# CircuitSupply_v1_0_3.net
KiCad netlist of a schematic drawn in EasyEDA Pro
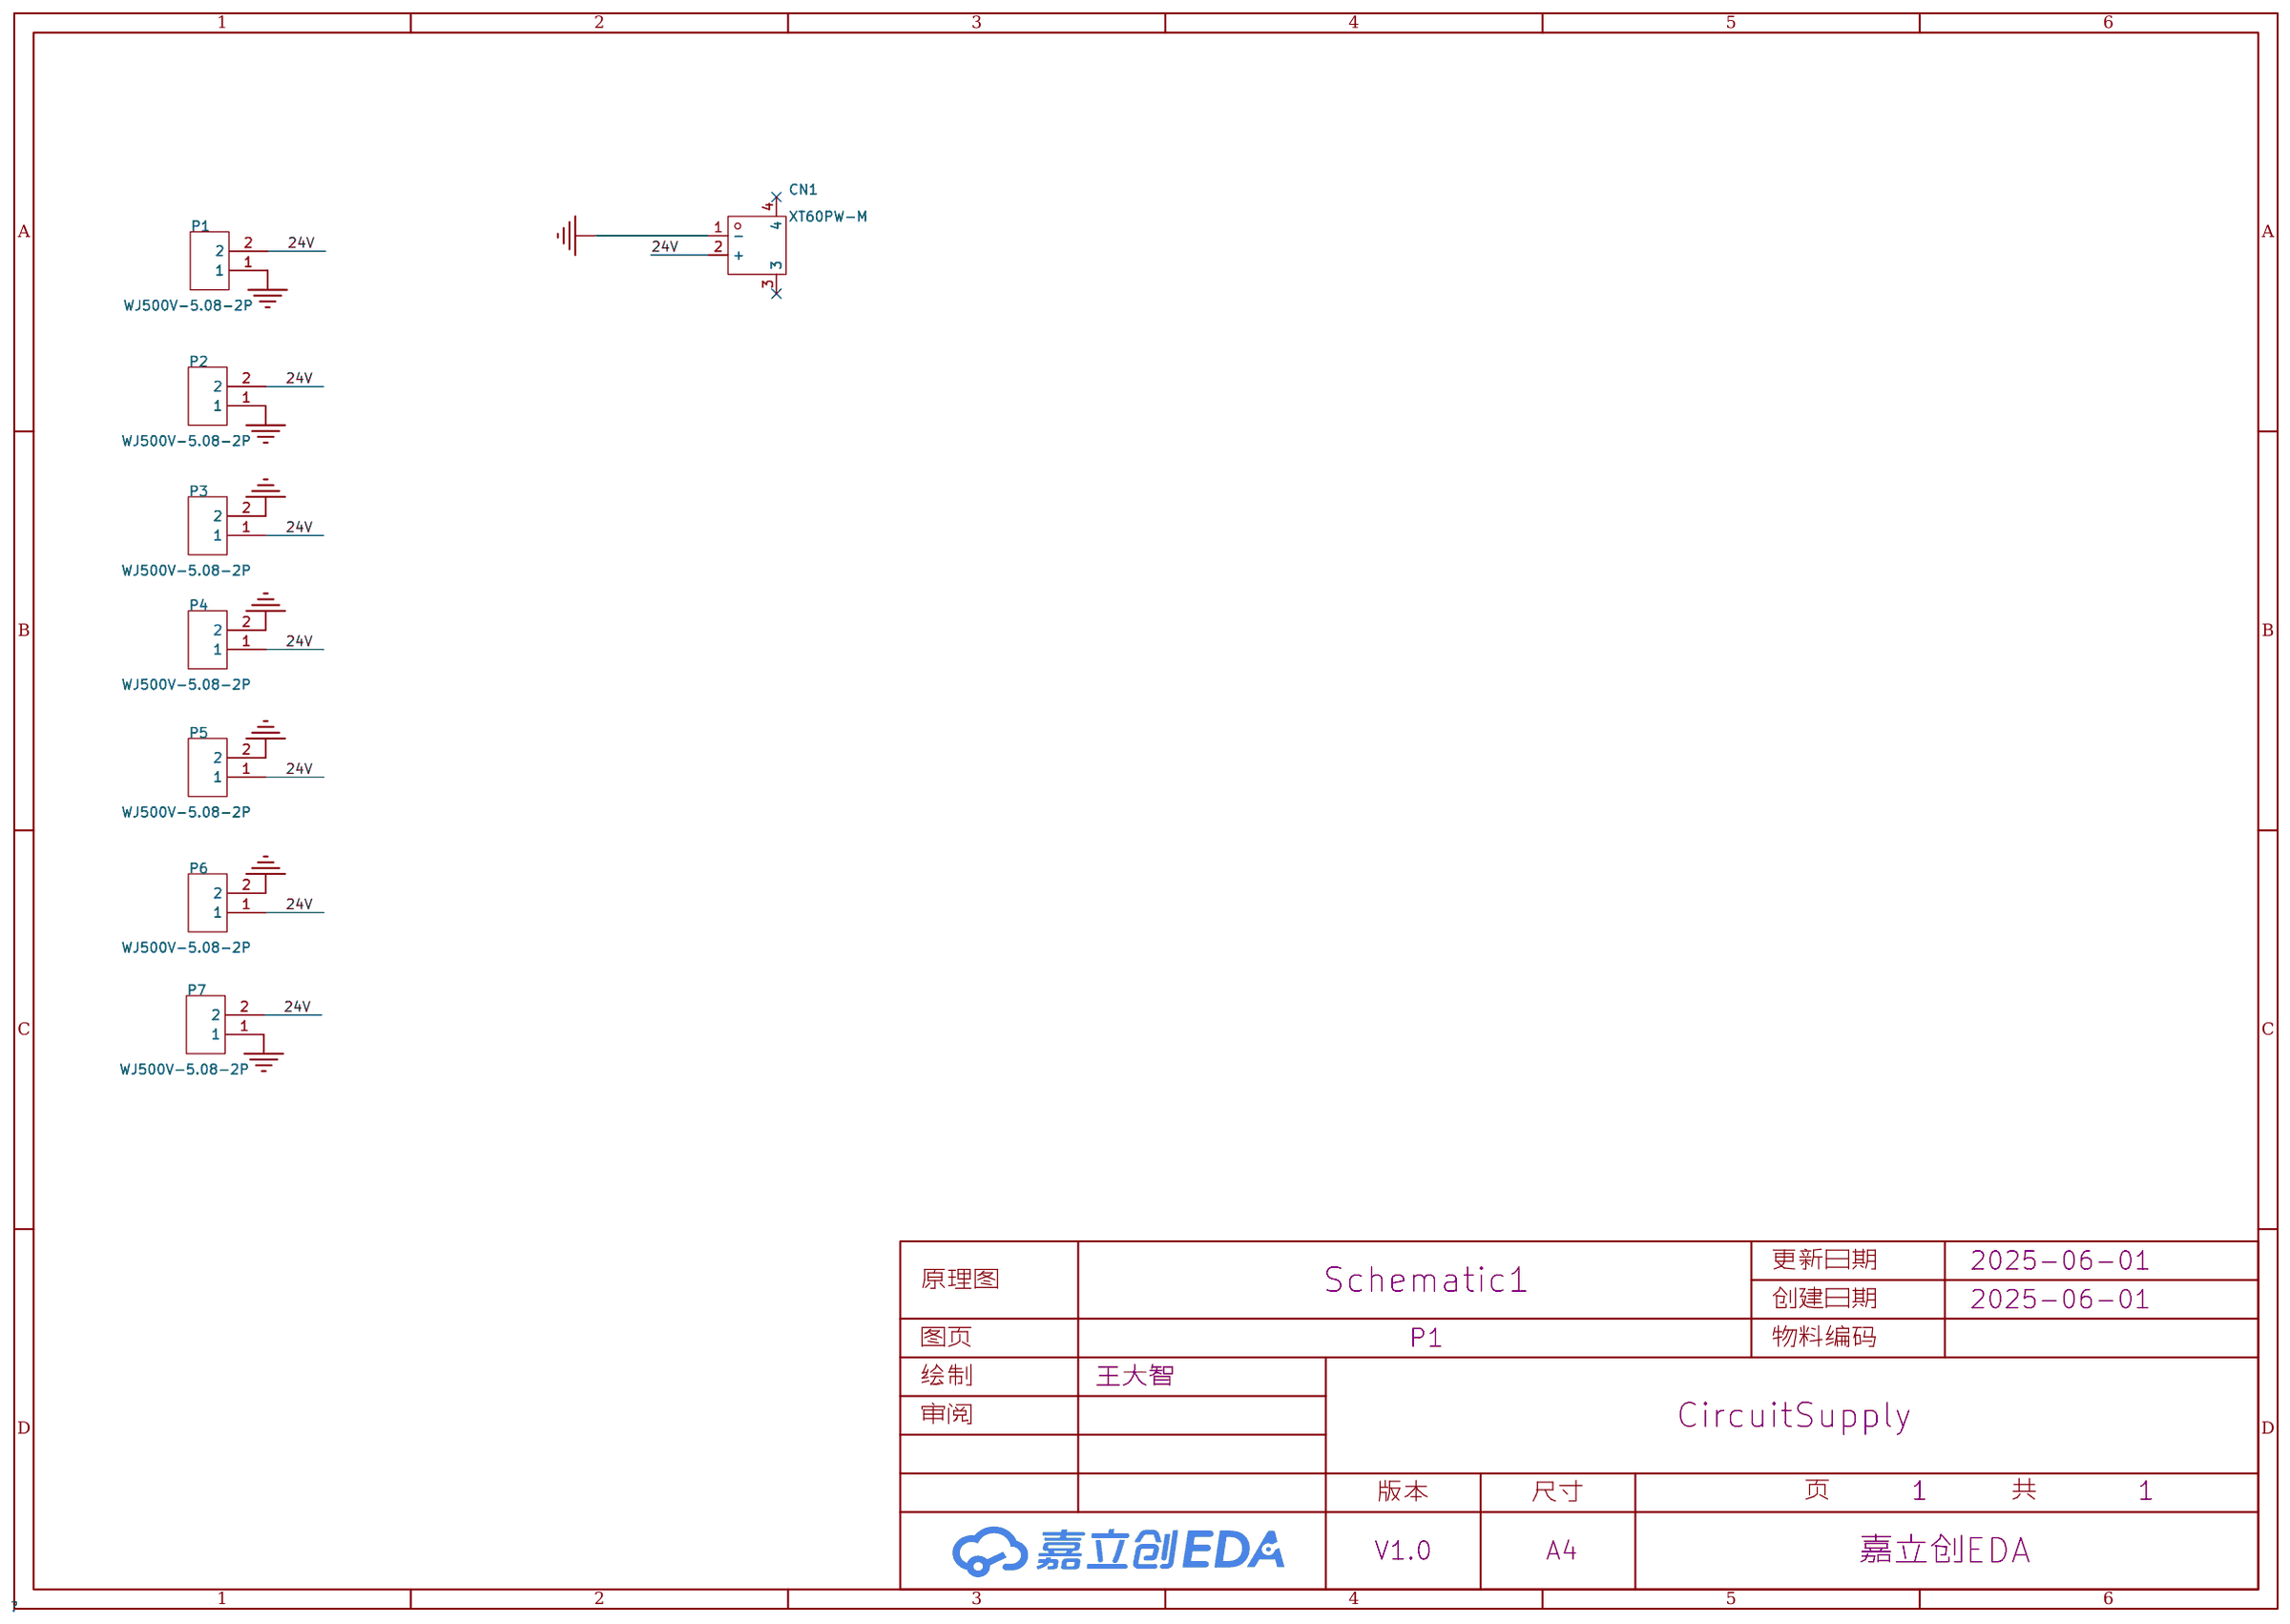
[diagram p0: schematic sheet]

(export (version "E")
  (design (tool "Eeschema 10.0.6"))
  (components
    (comp (ref "CN1")
      (value "XT60PW-M")
      (footprint "easyedapro:CONN-TH_XT60PW-M")
      (description "类别:-;类型1:-;")
      (fields (field (name "Manufacturer") "AMASS(艾迈斯)"))
      (libsource (lib "easyedapro") (part "XT60PW-M"))
    )
    (comp (ref "P1")
      (value "WJ500V-5.08-2P")
      (footprint "easyedapro:CONN-TH_2P-P5.00_WJ500V-5.08-2P")
      (fields (field (name "Manufacturer") "KANGNEX(康奈克斯电气)"))
      (libsource (lib "easyedapro") (part "WJ500V-5.08-2P-14-00A"))
    )
    (comp (ref "P2")
      (value "WJ500V-5.08-2P")
      (footprint "easyedapro:CONN-TH_2P-P5.00_WJ500V-5.08-2P")
      (fields (field (name "Manufacturer") "KANGNEX(康奈克斯电气)"))
      (libsource (lib "easyedapro") (part "WJ500V-5.08-2P-14-00A"))
    )
    (comp (ref "P3")
      (value "WJ500V-5.08-2P")
      (footprint "easyedapro:CONN-TH_2P-P5.00_WJ500V-5.08-2P")
      (fields (field (name "Manufacturer") "KANGNEX(康奈克斯电气)"))
      (libsource (lib "easyedapro") (part "WJ500V-5.08-2P-14-00A"))
    )
    (comp (ref "P4")
      (value "WJ500V-5.08-2P")
      (footprint "easyedapro:CONN-TH_2P-P5.00_WJ500V-5.08-2P")
      (fields (field (name "Manufacturer") "KANGNEX(康奈克斯电气)"))
      (libsource (lib "easyedapro") (part "WJ500V-5.08-2P-14-00A"))
    )
    (comp (ref "P5")
      (value "WJ500V-5.08-2P")
      (footprint "easyedapro:CONN-TH_2P-P5.00_WJ500V-5.08-2P")
      (fields (field (name "Manufacturer") "KANGNEX(康奈克斯电气)"))
      (libsource (lib "easyedapro") (part "WJ500V-5.08-2P-14-00A"))
    )
    (comp (ref "P6")
      (value "WJ500V-5.08-2P")
      (footprint "easyedapro:CONN-TH_2P-P5.00_WJ500V-5.08-2P")
      (fields (field (name "Manufacturer") "KANGNEX(康奈克斯电气)"))
      (libsource (lib "easyedapro") (part "WJ500V-5.08-2P-14-00A"))
    )
    (comp (ref "P7")
      (value "WJ500V-5.08-2P")
      (footprint "easyedapro:CONN-TH_2P-P5.00_WJ500V-5.08-2P")
      (fields (field (name "Manufacturer") "KANGNEX(康奈克斯电气)"))
      (libsource (lib "easyedapro") (part "WJ500V-5.08-2P-14-00A"))
    )
  )
  (nets
    (net (code "1") (name "/24V") (class "Default")
      (node (ref "CN1") (pin "2") (pinfunction "+_2") (pintype "unspecified"))
      (node (ref "P1") (pin "2") (pinfunction "2_2") (pintype "unspecified"))
      (node (ref "P2") (pin "2") (pinfunction "2_2") (pintype "unspecified"))
      (node (ref "P3") (pin "1") (pinfunction "1_1") (pintype "unspecified"))
      (node (ref "P4") (pin "1") (pinfunction "1_1") (pintype "unspecified"))
      (node (ref "P5") (pin "1") (pinfunction "1_1") (pintype "unspecified"))
      (node (ref "P6") (pin "1") (pinfunction "1_1") (pintype "unspecified"))
      (node (ref "P7") (pin "2") (pinfunction "2_2") (pintype "unspecified"))
    )
    (net (code "2") (name "GND") (class "Default")
      (node (ref "CN1") (pin "1") (pinfunction "-_1") (pintype "unspecified"))
      (node (ref "P1") (pin "1") (pinfunction "1_1") (pintype "unspecified"))
      (node (ref "P2") (pin "1") (pinfunction "1_1") (pintype "unspecified"))
      (node (ref "P3") (pin "2") (pinfunction "2_2") (pintype "unspecified"))
      (node (ref "P4") (pin "2") (pinfunction "2_2") (pintype "unspecified"))
      (node (ref "P5") (pin "2") (pinfunction "2_2") (pintype "unspecified"))
      (node (ref "P6") (pin "2") (pinfunction "2_2") (pintype "unspecified"))
      (node (ref "P7") (pin "1") (pinfunction "1_1") (pintype "unspecified"))
    )
    (net (code "3") (name "unconnected-(CN1-Pad3)") (class "Default")
      (node (ref "CN1") (pin "3") (pinfunction "3_3") (pintype "unspecified+no_connect"))
    )
    (net (code "4") (name "unconnected-(CN1-Pad4)") (class "Default")
      (node (ref "CN1") (pin "4") (pinfunction "4_4") (pintype "unspecified+no_connect"))
    )
  )
)
